# M0plus_breakout.net
KiCad netlist of a schematic drawn in EAGLE
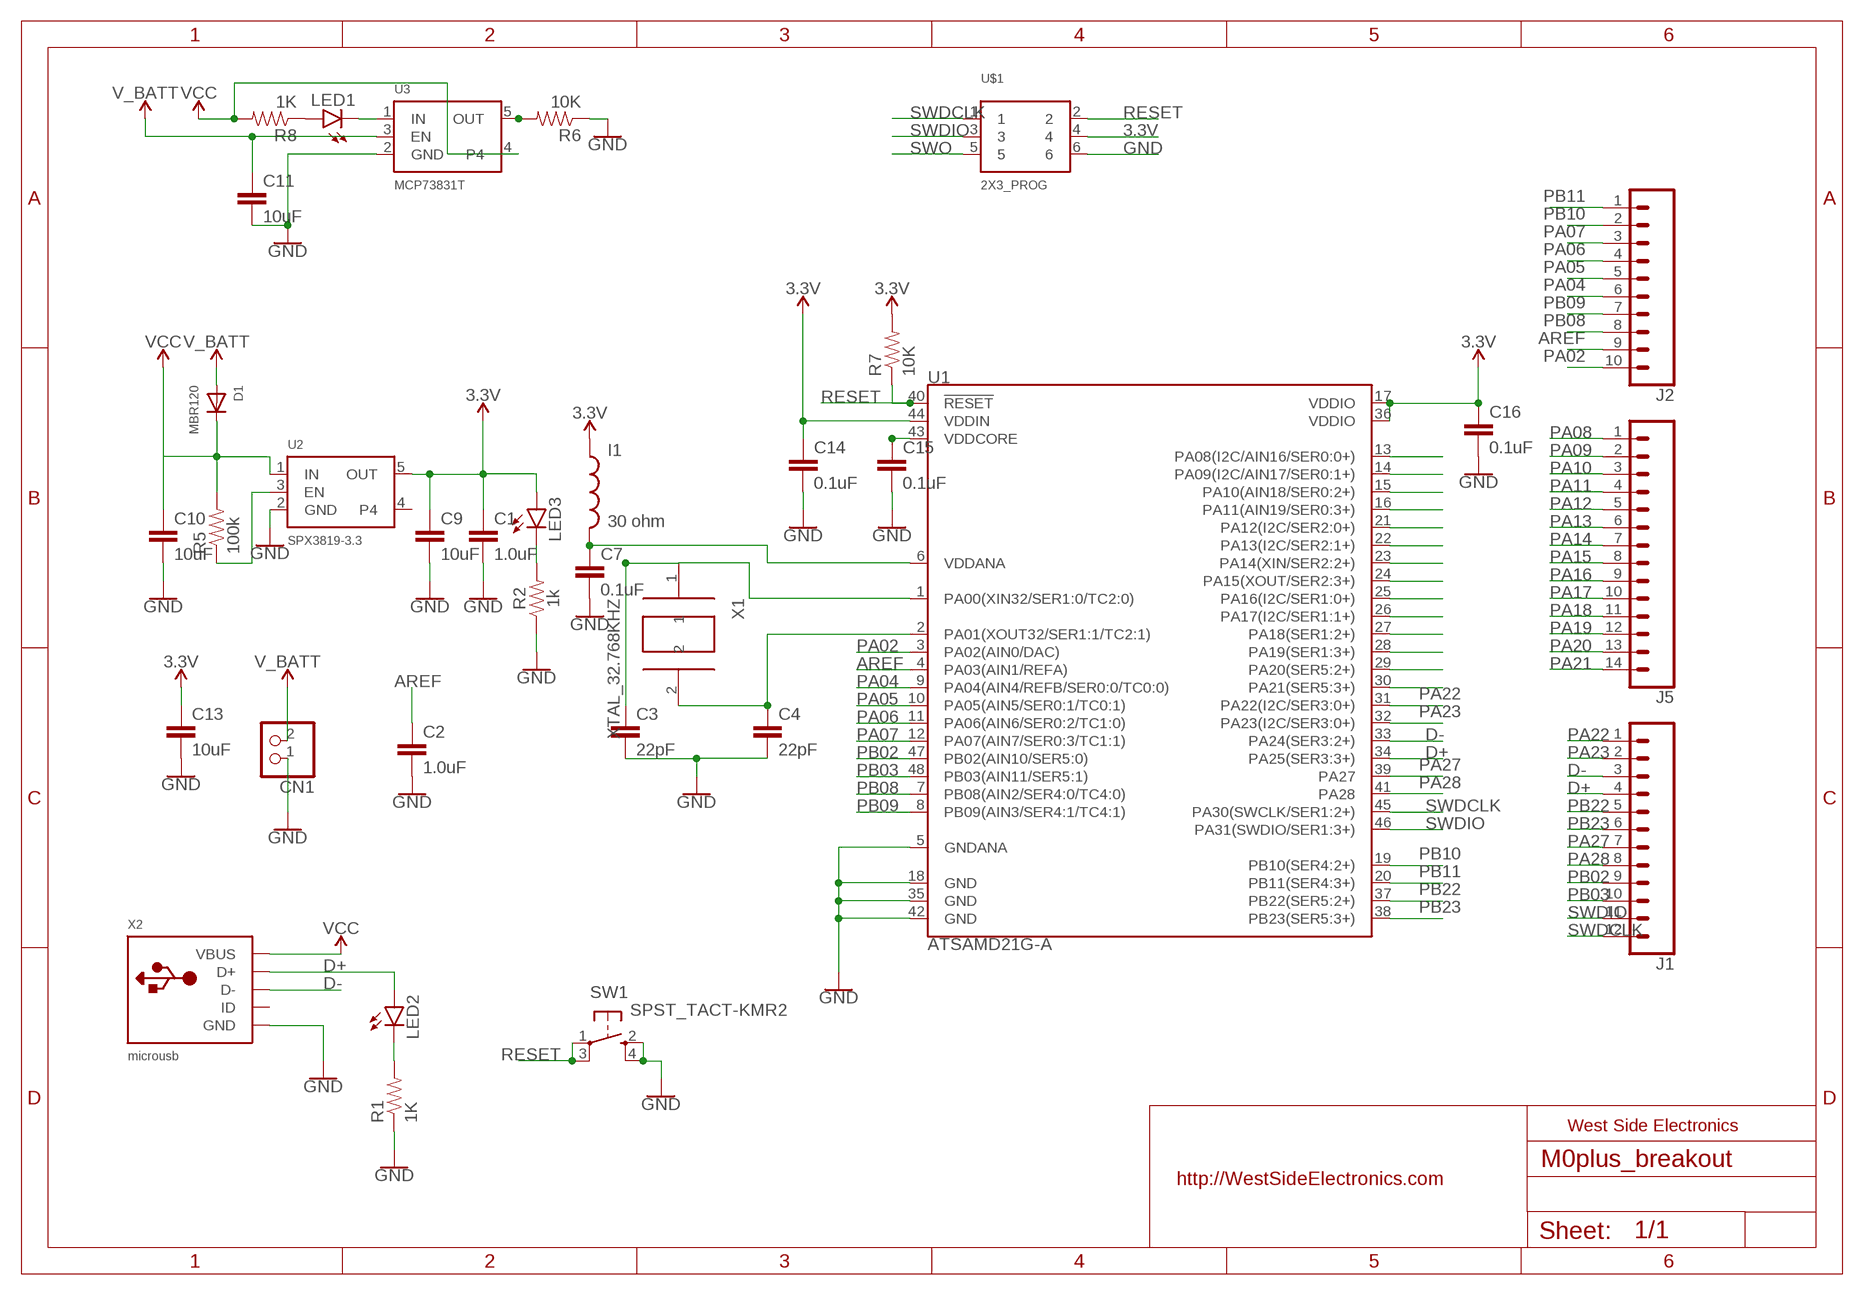
[diagram p0: schematic, sheet 1]

(export (version "E")
  (design (tool "Eeschema 10.0.6"))
  (components
    (comp (ref "C1")
      (value "1.0uF")
      (footprint "eagle-import:0603-CAP")
      (libsource (lib "eagle-import") (part "1.0UF-16V-10%(0603)"))
    )
    (comp (ref "C2")
      (value "1.0uF")
      (footprint "eagle-import:0603-CAP")
      (libsource (lib "eagle-import") (part "1.0UF-16V-10%(0603)"))
    )
    (comp (ref "C3")
      (value "22pF")
      (footprint "eagle-import:0603-CAP")
      (libsource (lib "eagle-import") (part "22PF-50V-5%(0603)"))
    )
    (comp (ref "C4")
      (value "22pF")
      (footprint "eagle-import:0603-CAP")
      (libsource (lib "eagle-import") (part "22PF-50V-5%(0603)"))
    )
    (comp (ref "C7")
      (value "0.1uF")
      (footprint "eagle-import:0805")
      (libsource (lib "eagle-import") (part "CAP"))
    )
    (comp (ref "C9")
      (value "10uF")
      (footprint "eagle-import:0805")
      (libsource (lib "eagle-import") (part "CAP"))
    )
    (comp (ref "C10")
      (value "10uF")
      (footprint "eagle-import:0805")
      (libsource (lib "eagle-import") (part "CAP"))
    )
    (comp (ref "C11")
      (value "10uF")
      (footprint "eagle-import:0805")
      (libsource (lib "eagle-import") (part "CAP"))
    )
    (comp (ref "C13")
      (value "10uF")
      (footprint "eagle-import:0805")
      (libsource (lib "eagle-import") (part "CAP"))
    )
    (comp (ref "C14")
      (value "0.1uF")
      (footprint "eagle-import:0603-CAP")
      (libsource (lib "eagle-import") (part "0.1UF-25V-5%(0603)"))
    )
    (comp (ref "C15")
      (value "0.1uF")
      (footprint "eagle-import:0603-CAP")
      (libsource (lib "eagle-import") (part "0.1UF-25V-5%(0603)"))
    )
    (comp (ref "C16")
      (value "0.1uF")
      (footprint "eagle-import:0603-CAP")
      (libsource (lib "eagle-import") (part "0.1UF-25V-5%(0603)"))
    )
    (comp (ref "CN1")
      (value "JST_2PIN")
      (footprint "eagle-import:JSTPH2")
      (libsource (lib "eagle-import") (part "JST_2PIN"))
    )
    (comp (ref "D1")
      (value "MBR120")
      (footprint "eagle-import:SOD-123")
      (libsource (lib "eagle-import") (part "DIODESOD-123"))
    )
    (comp (ref "I1")
      (value "30 ohm")
      (footprint "eagle-import:0805")
      (libsource (lib "eagle-import") (part "IND"))
    )
    (comp (ref "J1")
      (value "CONN_12")
      (footprint "eagle-import:1X12")
      (libsource (lib "eagle-import") (part "CONN_12"))
    )
    (comp (ref "J2")
      (value "CONN_10\"")
      (footprint "eagle-import:1X10")
      (libsource (lib "eagle-import") (part "CONN_10{dblquote}"))
    )
    (comp (ref "J5")
      (value "CONN_14")
      (footprint "eagle-import:1X14")
      (libsource (lib "eagle-import") (part "CONN_14"))
    )
    (comp (ref "LED1")
      (value "LED0603")
      (footprint "eagle-import:LED-0603")
      (libsource (lib "eagle-import") (part "LED0603"))
    )
    (comp (ref "LED2")
      (value "LED0603")
      (footprint "eagle-import:LED-0603")
      (libsource (lib "eagle-import") (part "LED0603"))
    )
    (comp (ref "LED3")
      (value "LED0603")
      (footprint "eagle-import:LED-0603")
      (libsource (lib "eagle-import") (part "LED0603"))
    )
    (comp (ref "R1")
      (value "1K")
      (footprint "eagle-import:0603-RES")
      (libsource (lib "eagle-import") (part "1KOHM-1/10W-1%(0603)"))
    )
    (comp (ref "R2")
      (value "1k")
      (footprint "eagle-import:0603")
      (libsource (lib "eagle-import") (part "1KOHM-0603-1/10W-1%"))
    )
    (comp (ref "R5")
      (value "100k")
      (footprint "eagle-import:0603-RES")
      (libsource (lib "eagle-import") (part "100KOHM-1/10W-1%(0603)"))
    )
    (comp (ref "R6")
      (value "10K")
      (footprint "eagle-import:0603-RES")
      (libsource (lib "eagle-import") (part "10KOHM-1/10W-1%(0603)0603"))
    )
    (comp (ref "R7")
      (value "10K")
      (footprint "eagle-import:0603-RES")
      (libsource (lib "eagle-import") (part "10KOHM-1/10W-1%(0603)0603"))
    )
    (comp (ref "R8")
      (value "1K")
      (footprint "eagle-import:0603-RES")
      (libsource (lib "eagle-import") (part "1KOHM-1/10W-1%(0603)"))
    )
    (comp (ref "SW1")
      (value "SPST_TACT-KMR2")
      (footprint "eagle-import:KMR2")
      (libsource (lib "eagle-import") (part "SPST_TACT-KMR2"))
    )
    (comp (ref "U$1")
      (value "2X3_PROG")
      (footprint "eagle-import:2X3-SMD_PROG")
      (libsource (lib "eagle-import") (part "2X3_PROG"))
    )
    (comp (ref "U1")
      (value "ATSAMD21G-A")
      (footprint "eagle-import:TQFP-48")
      (libsource (lib "eagle-import") (part "ATSAMD21G-A"))
    )
    (comp (ref "U2")
      (value "SPX3819-3.3")
      (footprint "eagle-import:SOT23-5")
      (libsource (lib "eagle-import") (part "VREG_SOT23-5"))
    )
    (comp (ref "U3")
      (value "MCP73831T")
      (footprint "eagle-import:SOT23-5")
      (libsource (lib "eagle-import") (part "VREG_SOT23-5"))
    )
    (comp (ref "X1")
      (value "XTAL_32.768KHZ")
      (footprint "eagle-import:ABS07-32.768KHZ-9-T")
      (libsource (lib "eagle-import") (part "XTAL_32.768KHZ"))
    )
    (comp (ref "X2")
      (value "microusb")
      (footprint "eagle-import:4UCONN_20329_V2")
      (libsource (lib "eagle-import") (part "USB_MICRO_20329_V2"))
    )
  )
  (nets
    (net (code "1") (name "/AREF") (class "Default")
      (node (ref "C2") (pin "1") (pinfunction "1_1") (pintype "passive"))
      (node (ref "J2") (pin "9") (pinfunction "9_9") (pintype "passive"))
      (node (ref "U1") (pin "4") (pinfunction "PA03(AIN1/REFA)_4") (pintype "bidirectional"))
    )
    (net (code "2") (name "/D+") (class "Default")
      (node (ref "J1") (pin "4") (pinfunction "4_4") (pintype "passive"))
      (node (ref "LED2") (pin "A") (pinfunction "A_A") (pintype "passive"))
      (node (ref "U1") (pin "34") (pinfunction "PA25(SER3:3+)_34") (pintype "bidirectional"))
      (node (ref "X2") (pin "D+") (pinfunction "D+_D+") (pintype "bidirectional"))
    )
    (net (code "3") (name "/D-") (class "Default")
      (node (ref "J1") (pin "3") (pinfunction "3_3") (pintype "passive"))
      (node (ref "U1") (pin "33") (pinfunction "PA24(SER3:2+)_33") (pintype "bidirectional"))
      (node (ref "X2") (pin "D-") (pinfunction "D-_D-") (pintype "bidirectional"))
    )
    (net (code "4") (name "/PA02") (class "Default")
      (node (ref "J2") (pin "10") (pinfunction "10_10") (pintype "passive"))
      (node (ref "U1") (pin "3") (pinfunction "PA02(AIN0/DAC)_3") (pintype "bidirectional"))
    )
    (net (code "5") (name "/PA04") (class "Default")
      (node (ref "J2") (pin "6") (pinfunction "6_6") (pintype "passive"))
      (node (ref "U1") (pin "9") (pinfunction "PA04(AIN4/REFB/SER0:0/TC0:0)_9") (pintype "bidirectional"))
    )
    (net (code "6") (name "/PA05") (class "Default")
      (node (ref "J2") (pin "5") (pinfunction "5_5") (pintype "passive"))
      (node (ref "U1") (pin "10") (pinfunction "PA05(AIN5/SER0:1/TC0:1)_10") (pintype "bidirectional"))
    )
    (net (code "7") (name "/PA06") (class "Default")
      (node (ref "J2") (pin "4") (pinfunction "4_4") (pintype "passive"))
      (node (ref "U1") (pin "11") (pinfunction "PA06(AIN6/SER0:2/TC1:0)_11") (pintype "bidirectional"))
    )
    (net (code "8") (name "/PA07") (class "Default")
      (node (ref "J2") (pin "3") (pinfunction "3_3") (pintype "passive"))
      (node (ref "U1") (pin "12") (pinfunction "PA07(AIN7/SER0:3/TC1:1)_12") (pintype "bidirectional"))
    )
    (net (code "9") (name "/PA08") (class "Default")
      (node (ref "J5") (pin "1") (pinfunction "1_1") (pintype "passive"))
      (node (ref "U1") (pin "13") (pinfunction "PA08(I2C/AIN16/SER0:0+)_13") (pintype "bidirectional"))
    )
    (net (code "10") (name "/PA09") (class "Default")
      (node (ref "J5") (pin "2") (pinfunction "2_2") (pintype "passive"))
      (node (ref "U1") (pin "14") (pinfunction "PA09(I2C/AIN17/SER0:1+)_14") (pintype "bidirectional"))
    )
    (net (code "11") (name "/PA10") (class "Default")
      (node (ref "J5") (pin "3") (pinfunction "3_3") (pintype "passive"))
      (node (ref "U1") (pin "15") (pinfunction "PA10(AIN18/SER0:2+)_15") (pintype "bidirectional"))
    )
    (net (code "12") (name "/PA11") (class "Default")
      (node (ref "J5") (pin "4") (pinfunction "4_4") (pintype "passive"))
      (node (ref "U1") (pin "16") (pinfunction "PA11(AIN19/SER0:3+)_16") (pintype "bidirectional"))
    )
    (net (code "13") (name "/PA12") (class "Default")
      (node (ref "J5") (pin "5") (pinfunction "5_5") (pintype "passive"))
      (node (ref "U1") (pin "21") (pinfunction "PA12(I2C/SER2:0+)_21") (pintype "bidirectional"))
    )
    (net (code "14") (name "/PA13") (class "Default")
      (node (ref "J5") (pin "6") (pinfunction "6_6") (pintype "passive"))
      (node (ref "U1") (pin "22") (pinfunction "PA13(I2C/SER2:1+)_22") (pintype "bidirectional"))
    )
    (net (code "15") (name "/PA14") (class "Default")
      (node (ref "J5") (pin "7") (pinfunction "7_7") (pintype "passive"))
      (node (ref "U1") (pin "23") (pinfunction "PA14(XIN/SER2:2+)_23") (pintype "bidirectional"))
    )
    (net (code "16") (name "/PA15") (class "Default")
      (node (ref "J5") (pin "8") (pinfunction "8_8") (pintype "passive"))
      (node (ref "U1") (pin "24") (pinfunction "PA15(XOUT/SER2:3+)_24") (pintype "bidirectional"))
    )
    (net (code "17") (name "/PA16") (class "Default")
      (node (ref "J5") (pin "9") (pinfunction "9_9") (pintype "passive"))
      (node (ref "U1") (pin "25") (pinfunction "PA16(I2C/SER1:0+)_25") (pintype "bidirectional"))
    )
    (net (code "18") (name "/PA17") (class "Default")
      (node (ref "J5") (pin "10") (pinfunction "10_10") (pintype "passive"))
      (node (ref "U1") (pin "26") (pinfunction "PA17(I2C/SER1:1+)_26") (pintype "bidirectional"))
    )
    (net (code "19") (name "/PA18") (class "Default")
      (node (ref "J5") (pin "11") (pinfunction "11_11") (pintype "passive"))
      (node (ref "U1") (pin "27") (pinfunction "PA18(SER1:2+)_27") (pintype "bidirectional"))
    )
    (net (code "20") (name "/PA19") (class "Default")
      (node (ref "J5") (pin "12") (pinfunction "12_12") (pintype "passive"))
      (node (ref "U1") (pin "28") (pinfunction "PA19(SER1:3+)_28") (pintype "bidirectional"))
    )
    (net (code "21") (name "/PA20") (class "Default")
      (node (ref "J5") (pin "13") (pinfunction "13_13") (pintype "passive"))
      (node (ref "U1") (pin "29") (pinfunction "PA20(SER5:2+)_29") (pintype "bidirectional"))
    )
    (net (code "22") (name "/PA21") (class "Default")
      (node (ref "J5") (pin "14") (pinfunction "14_14") (pintype "passive"))
      (node (ref "U1") (pin "30") (pinfunction "PA21(SER5:3+)_30") (pintype "bidirectional"))
    )
    (net (code "23") (name "/PA22") (class "Default")
      (node (ref "J1") (pin "1") (pinfunction "1_1") (pintype "passive"))
      (node (ref "U1") (pin "31") (pinfunction "PA22(I2C/SER3:0+)_31") (pintype "bidirectional"))
    )
    (net (code "24") (name "/PA23") (class "Default")
      (node (ref "J1") (pin "2") (pinfunction "2_2") (pintype "passive"))
      (node (ref "U1") (pin "32") (pinfunction "PA23(I2C/SER3:0+)_32") (pintype "bidirectional"))
    )
    (net (code "25") (name "/PA27") (class "Default")
      (node (ref "J1") (pin "7") (pinfunction "7_7") (pintype "passive"))
      (node (ref "U1") (pin "39") (pinfunction "PA27_39") (pintype "bidirectional"))
    )
    (net (code "26") (name "/PA28") (class "Default")
      (node (ref "J1") (pin "8") (pinfunction "8_8") (pintype "passive"))
      (node (ref "U1") (pin "41") (pinfunction "PA28_41") (pintype "bidirectional"))
    )
    (net (code "27") (name "/PB02") (class "Default")
      (node (ref "J1") (pin "9") (pinfunction "9_9") (pintype "passive"))
      (node (ref "U1") (pin "47") (pinfunction "PB02(AIN10/SER5:0)_47") (pintype "bidirectional"))
    )
    (net (code "28") (name "/PB03") (class "Default")
      (node (ref "J1") (pin "10") (pinfunction "10_10") (pintype "passive"))
      (node (ref "U1") (pin "48") (pinfunction "PB03(AIN11/SER5:1)_48") (pintype "bidirectional"))
    )
    (net (code "29") (name "/PB08") (class "Default")
      (node (ref "J2") (pin "8") (pinfunction "8_8") (pintype "passive"))
      (node (ref "U1") (pin "7") (pinfunction "PB08(AIN2/SER4:0/TC4:0)_7") (pintype "bidirectional"))
    )
    (net (code "30") (name "/PB09") (class "Default")
      (node (ref "J2") (pin "7") (pinfunction "7_7") (pintype "passive"))
      (node (ref "U1") (pin "8") (pinfunction "PB09(AIN3/SER4:1/TC4:1)_8") (pintype "bidirectional"))
    )
    (net (code "31") (name "/PB10") (class "Default")
      (node (ref "J2") (pin "2") (pinfunction "2_2") (pintype "passive"))
      (node (ref "U1") (pin "19") (pinfunction "PB10(SER4:2+)_19") (pintype "bidirectional"))
    )
    (net (code "32") (name "/PB11") (class "Default")
      (node (ref "J2") (pin "1") (pinfunction "1_1") (pintype "passive"))
      (node (ref "U1") (pin "20") (pinfunction "PB11(SER4:3+)_20") (pintype "bidirectional"))
    )
    (net (code "33") (name "/PB22") (class "Default")
      (node (ref "J1") (pin "5") (pinfunction "5_5") (pintype "passive"))
      (node (ref "U1") (pin "37") (pinfunction "PB22(SER5:2+)_37") (pintype "bidirectional"))
    )
    (net (code "34") (name "/PB23") (class "Default")
      (node (ref "J1") (pin "6") (pinfunction "6_6") (pintype "passive"))
      (node (ref "U1") (pin "38") (pinfunction "PB23(SER5:3+)_38") (pintype "bidirectional"))
    )
    (net (code "35") (name "/RESET") (class "Default")
      (node (ref "R7") (pin "1") (pinfunction "1_1") (pintype "passive"))
      (node (ref "SW1") (pin "1") (pinfunction "P_1") (pintype "passive"))
      (node (ref "SW1") (pin "3") (pinfunction "P1_3") (pintype "passive"))
      (node (ref "U$1") (pin "2") (pinfunction "2_2") (pintype "bidirectional"))
      (node (ref "U1") (pin "40") (pinfunction "~{RESET}_40") (pintype "bidirectional"))
    )
    (net (code "36") (name "/SWDCLK") (class "Default")
      (node (ref "J1") (pin "12") (pinfunction "12_12") (pintype "passive"))
      (node (ref "U$1") (pin "1") (pinfunction "1_1") (pintype "bidirectional"))
      (node (ref "U1") (pin "45") (pinfunction "PA30(SWCLK/SER1:2+)_45") (pintype "bidirectional"))
    )
    (net (code "37") (name "/SWDIO") (class "Default")
      (node (ref "J1") (pin "11") (pinfunction "11_11") (pintype "passive"))
      (node (ref "U$1") (pin "3") (pinfunction "3_3") (pintype "bidirectional"))
      (node (ref "U1") (pin "46") (pinfunction "PA31(SWDIO/SER1:3+)_46") (pintype "bidirectional"))
    )
    (net (code "38") (name "/SWO") (class "Default")
      (node (ref "U$1") (pin "5") (pinfunction "5_5") (pintype "bidirectional"))
    )
    (net (code "39") (name "3.3V") (class "Default")
      (node (ref "C1") (pin "1") (pinfunction "1_1") (pintype "passive"))
      (node (ref "C13") (pin "1") (pinfunction "1_1") (pintype "passive"))
      (node (ref "C14") (pin "1") (pinfunction "1_1") (pintype "passive"))
      (node (ref "C16") (pin "1") (pinfunction "1_1") (pintype "passive"))
      (node (ref "C9") (pin "1") (pinfunction "1_1") (pintype "passive"))
      (node (ref "I1") (pin "1") (pinfunction "1_1") (pintype "passive"))
      (node (ref "LED3") (pin "A") (pinfunction "A_A") (pintype "passive"))
      (node (ref "R7") (pin "2") (pinfunction "2_2") (pintype "passive"))
      (node (ref "U$1") (pin "4") (pinfunction "4_4") (pintype "bidirectional"))
      (node (ref "U1") (pin "17") (pinfunction "VDDIO_17") (pintype "bidirectional"))
      (node (ref "U1") (pin "36") (pinfunction "VDDIO_36") (pintype "bidirectional"))
      (node (ref "U1") (pin "44") (pinfunction "VDDIN_44") (pintype "bidirectional"))
      (node (ref "U2") (pin "5") (pinfunction "OUT_5") (pintype "bidirectional"))
    )
    (net (code "40") (name "GND") (class "Default")
      (node (ref "C1") (pin "2") (pinfunction "2_2") (pintype "passive"))
      (node (ref "C10") (pin "2") (pinfunction "2_2") (pintype "passive"))
      (node (ref "C11") (pin "2") (pinfunction "2_2") (pintype "passive"))
      (node (ref "C13") (pin "2") (pinfunction "2_2") (pintype "passive"))
      (node (ref "C14") (pin "2") (pinfunction "2_2") (pintype "passive"))
      (node (ref "C15") (pin "2") (pinfunction "2_2") (pintype "passive"))
      (node (ref "C16") (pin "2") (pinfunction "2_2") (pintype "passive"))
      (node (ref "C2") (pin "2") (pinfunction "2_2") (pintype "passive"))
      (node (ref "C3") (pin "2") (pinfunction "2_2") (pintype "passive"))
      (node (ref "C4") (pin "2") (pinfunction "2_2") (pintype "passive"))
      (node (ref "C7") (pin "2") (pinfunction "2_2") (pintype "passive"))
      (node (ref "C9") (pin "2") (pinfunction "2_2") (pintype "passive"))
      (node (ref "CN1") (pin "1") (pinfunction "1_1") (pintype "passive"))
      (node (ref "R1") (pin "1") (pinfunction "1_1") (pintype "passive"))
      (node (ref "R2") (pin "1") (pinfunction "1_1") (pintype "passive"))
      (node (ref "R6") (pin "1") (pinfunction "1_1") (pintype "passive"))
      (node (ref "SW1") (pin "2") (pinfunction "S_2") (pintype "passive"))
      (node (ref "SW1") (pin "4") (pinfunction "S1_4") (pintype "passive"))
      (node (ref "U$1") (pin "6") (pinfunction "6_6") (pintype "bidirectional"))
      (node (ref "U1") (pin "18") (pinfunction "GND_18") (pintype "bidirectional"))
      (node (ref "U1") (pin "35") (pinfunction "GND_35") (pintype "bidirectional"))
      (node (ref "U1") (pin "42") (pinfunction "GND_42") (pintype "bidirectional"))
      (node (ref "U1") (pin "5") (pinfunction "GNDANA_5") (pintype "bidirectional"))
      (node (ref "U2") (pin "2") (pinfunction "GND_2") (pintype "bidirectional"))
      (node (ref "U3") (pin "2") (pinfunction "GND_2") (pintype "bidirectional"))
      (node (ref "X2") (pin "BASE@1") (pinfunction "GND_BASE@1") (pintype "power_in"))
      (node (ref "X2") (pin "BASE@2") (pinfunction "GND_BASE@2") (pintype "power_in"))
      (node (ref "X2") (pin "GND") (pinfunction "GND_GND") (pintype "power_in"))
      (node (ref "X2") (pin "SPRT@1") (pinfunction "GND_SPRT@1") (pintype "power_in"))
      (node (ref "X2") (pin "SPRT@2") (pinfunction "GND_SPRT@2") (pintype "power_in"))
      (node (ref "X2") (pin "SPRT@3") (pinfunction "GND_SPRT@3") (pintype "power_in"))
      (node (ref "X2") (pin "SPRT@4") (pinfunction "GND_SPRT@4") (pintype "power_in"))
    )
    (net (code "41") (name "Net-(LED1-PadA)") (class "Default")
      (node (ref "LED1") (pin "A") (pinfunction "A_A") (pintype "passive"))
      (node (ref "R8") (pin "1") (pinfunction "1_1") (pintype "passive"))
    )
    (net (code "42") (name "Net-(LED2-PadC)") (class "Default")
      (node (ref "LED2") (pin "C") (pinfunction "C_C") (pintype "passive"))
      (node (ref "R1") (pin "2") (pinfunction "2_2") (pintype "passive"))
    )
    (net (code "43") (name "Net-(LED3-PadC)") (class "Default")
      (node (ref "LED3") (pin "C") (pinfunction "C_C") (pintype "passive"))
      (node (ref "R2") (pin "2") (pinfunction "2_2") (pintype "passive"))
    )
    (net (code "44") (name "Net-(U1-PA00(XIN32{slash}SER1:0{slash}TC2:0))") (class "Default")
      (node (ref "C3") (pin "1") (pinfunction "1_1") (pintype "passive"))
      (node (ref "U1") (pin "1") (pinfunction "PA00(XIN32/SER1:0/TC2:0)_1") (pintype "bidirectional"))
      (node (ref "X1") (pin "1") (pinfunction "1_1") (pintype "bidirectional"))
    )
    (net (code "45") (name "Net-(U1-PA01(XOUT32{slash}SER1:1{slash}TC2:1))") (class "Default")
      (node (ref "C4") (pin "1") (pinfunction "1_1") (pintype "passive"))
      (node (ref "U1") (pin "2") (pinfunction "PA01(XOUT32/SER1:1/TC2:1)_2") (pintype "bidirectional"))
      (node (ref "X1") (pin "2") (pinfunction "2_2") (pintype "bidirectional"))
    )
    (net (code "46") (name "Net-(U1-VDDANA)") (class "Default")
      (node (ref "C7") (pin "1") (pinfunction "1_1") (pintype "passive"))
      (node (ref "I1") (pin "2") (pinfunction "2_2") (pintype "passive"))
      (node (ref "U1") (pin "6") (pinfunction "VDDANA_6") (pintype "bidirectional"))
    )
    (net (code "47") (name "Net-(U1-VDDCORE)") (class "Default")
      (node (ref "C15") (pin "1") (pinfunction "1_1") (pintype "passive"))
      (node (ref "U1") (pin "43") (pinfunction "VDDCORE_43") (pintype "bidirectional"))
    )
    (net (code "48") (name "Net-(U2-EN)") (class "Default")
      (node (ref "R5") (pin "1") (pinfunction "1_1") (pintype "passive"))
      (node (ref "U2") (pin "3") (pinfunction "EN_3") (pintype "bidirectional"))
    )
    (net (code "49") (name "Net-(U3-IN)") (class "Default")
      (node (ref "LED1") (pin "C") (pinfunction "C_C") (pintype "passive"))
      (node (ref "U3") (pin "1") (pinfunction "IN_1") (pintype "bidirectional"))
    )
    (net (code "50") (name "Net-(U3-OUT)") (class "Default")
      (node (ref "R6") (pin "2") (pinfunction "2_2") (pintype "passive"))
      (node (ref "U3") (pin "5") (pinfunction "OUT_5") (pintype "bidirectional"))
    )
    (net (code "51") (name "VCC") (class "Default")
      (node (ref "C10") (pin "1") (pinfunction "1_1") (pintype "passive"))
      (node (ref "D1") (pin "C") (pinfunction "C_C") (pintype "passive"))
      (node (ref "R5") (pin "2") (pinfunction "2_2") (pintype "passive"))
      (node (ref "R8") (pin "2") (pinfunction "2_2") (pintype "passive"))
      (node (ref "U2") (pin "1") (pinfunction "IN_1") (pintype "bidirectional"))
      (node (ref "U3") (pin "4") (pinfunction "P4_4") (pintype "bidirectional"))
      (node (ref "X2") (pin "VBUS") (pinfunction "VBUS_VBUS") (pintype "power_in"))
    )
    (net (code "52") (name "V_BATT") (class "Default")
      (node (ref "C11") (pin "1") (pinfunction "1_1") (pintype "passive"))
      (node (ref "CN1") (pin "2") (pinfunction "2_2") (pintype "passive"))
      (node (ref "D1") (pin "A") (pinfunction "A_A") (pintype "passive"))
      (node (ref "U3") (pin "3") (pinfunction "EN_3") (pintype "bidirectional"))
    )
    (net (code "53") (name "unconnected-(U2-P4-Pad4)") (class "Default")
      (node (ref "U2") (pin "4") (pinfunction "P4_4") (pintype "bidirectional"))
    )
    (net (code "54") (name "unconnected-(X2-PadID)") (class "Default")
      (node (ref "X2") (pin "ID") (pinfunction "ID_ID") (pintype "bidirectional"))
    )
  )
)
